# radio.net
KiCad netlist of a schematic drawn in Altium Designer
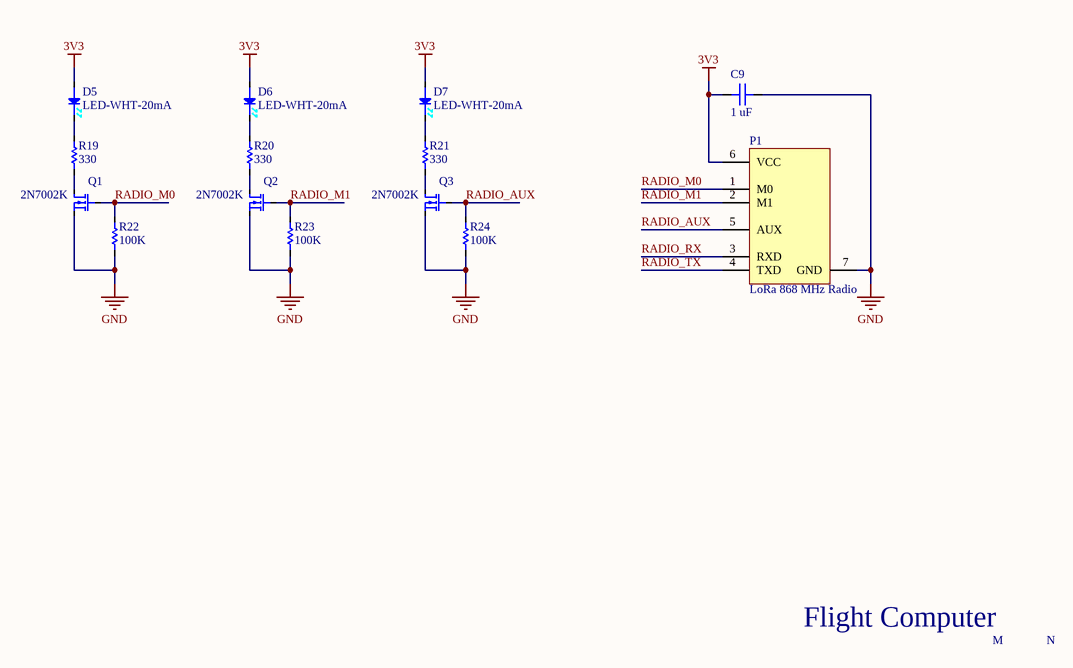
[diagram p0: radio.SchDoc]

(export (version "E")
  (design (tool "Eeschema 10.0.6"))
  (components
    (comp (ref "C9")
      (value "1 uF")
      (footprint "CAP-CER-0805-TALL")
      (description "±10%, 0805")
      (libsource (lib "passive") (part "CAP-CER-1uF-10V"))
    )
    (comp (ref "D5")
      (value "LED-WHT-20mA")
      (footprint "LED-0805")
      (description "2.2V, 0805")
      (libsource (lib "passive") (part "LED-WHT-20mA"))
    )
    (comp (ref "D6")
      (value "LED-WHT-20mA")
      (footprint "LED-0805")
      (description "2.2V, 0805")
      (libsource (lib "passive") (part "LED-WHT-20mA"))
    )
    (comp (ref "D7")
      (value "LED-WHT-20mA")
      (footprint "LED-0805")
      (description "2.2V, 0805")
      (libsource (lib "passive") (part "LED-WHT-20mA"))
    )
    (comp (ref "P1")
      (value "LoRa 868 MHz Radio")
      (footprint "LoRa Breakout")
      (description "UART Interface, 0.1\" Pitch, E32 (868T20D) chipset")
      (libsource (lib "connector") (part "868 MHz SX1276 LoRa Breakout"))
    )
    (comp (ref "Q1")
      (value "2N7002K")
      (footprint "SC-89")
      (description "N-Channel, SOT-23")
      (libsource (lib "ic") (part "NMOS-2.0VT-60VDS-300mA"))
    )
    (comp (ref "Q2")
      (value "2N7002K")
      (footprint "SC-89")
      (description "N-Channel, SOT-23")
      (libsource (lib "ic") (part "NMOS-2.0VT-60VDS-300mA"))
    )
    (comp (ref "Q3")
      (value "2N7002K")
      (footprint "SC-89")
      (description "N-Channel, SOT-23")
      (libsource (lib "ic") (part "NMOS-2.0VT-60VDS-300mA"))
    )
    (comp (ref "R19")
      (value "330")
      (footprint "RES-0805")
      (description "0805")
      (libsource (lib "passive") (part "RES-330-1/8W"))
    )
    (comp (ref "R20")
      (value "330")
      (footprint "RES-0805")
      (description "0805")
      (libsource (lib "passive") (part "RES-330-1/8W"))
    )
    (comp (ref "R21")
      (value "330")
      (footprint "RES-0805")
      (description "0805")
      (libsource (lib "passive") (part "RES-330-1/8W"))
    )
    (comp (ref "R22")
      (value "100K")
      (footprint "RES-0805")
      (description "0805")
      (libsource (lib "passive") (part "RES-100K-1/8W"))
    )
    (comp (ref "R23")
      (value "100K")
      (footprint "RES-0805")
      (description "0805")
      (libsource (lib "passive") (part "RES-100K-1/8W"))
    )
    (comp (ref "R24")
      (value "100K")
      (footprint "RES-0805")
      (description "0805")
      (libsource (lib "passive") (part "RES-100K-1/8W"))
    )
  )
  (nets
    (net (code "1") (name "/RADIO_AUX") (class "Default")
      (node (ref "P1") (pin "5") (pinfunction "AUX_5") (pintype "passive"))
      (node (ref "Q3") (pin "1") (pinfunction "G_1") (pintype "passive"))
      (node (ref "R24") (pin "2") (pinfunction "2_2") (pintype "passive"))
    )
    (net (code "2") (name "/RADIO_M0") (class "Default")
      (node (ref "P1") (pin "1") (pinfunction "M0_1") (pintype "passive"))
      (node (ref "Q1") (pin "1") (pinfunction "G_1") (pintype "passive"))
      (node (ref "R22") (pin "2") (pinfunction "2_2") (pintype "passive"))
    )
    (net (code "3") (name "/RADIO_M1") (class "Default")
      (node (ref "P1") (pin "2") (pinfunction "M1_2") (pintype "passive"))
      (node (ref "Q2") (pin "1") (pinfunction "G_1") (pintype "passive"))
      (node (ref "R23") (pin "2") (pinfunction "2_2") (pintype "passive"))
    )
    (net (code "4") (name "/RADIO_RX") (class "Default")
      (node (ref "P1") (pin "3") (pinfunction "RXD_3") (pintype "passive"))
    )
    (net (code "5") (name "/RADIO_TX") (class "Default")
      (node (ref "P1") (pin "4") (pinfunction "TXD_4") (pintype "passive"))
    )
    (net (code "6") (name "3V3") (class "Default")
      (node (ref "C9") (pin "1") (pinfunction "1_1") (pintype "passive"))
      (node (ref "D5") (pin "1") (pinfunction "CT_1") (pintype "passive"))
      (node (ref "D6") (pin "1") (pinfunction "CT_1") (pintype "passive"))
      (node (ref "D7") (pin "1") (pinfunction "CT_1") (pintype "passive"))
      (node (ref "P1") (pin "6") (pinfunction "VCC_6") (pintype "passive"))
    )
    (net (code "7") (name "GND") (class "Default")
      (node (ref "C9") (pin "2") (pinfunction "2_2") (pintype "passive"))
      (node (ref "P1") (pin "7") (pinfunction "GND_7") (pintype "passive"))
      (node (ref "Q1") (pin "2") (pinfunction "S_2") (pintype "passive"))
      (node (ref "Q2") (pin "2") (pinfunction "S_2") (pintype "passive"))
      (node (ref "Q3") (pin "2") (pinfunction "S_2") (pintype "passive"))
      (node (ref "R22") (pin "1") (pinfunction "1_1") (pintype "passive"))
      (node (ref "R23") (pin "1") (pinfunction "1_1") (pintype "passive"))
      (node (ref "R24") (pin "1") (pinfunction "1_1") (pintype "passive"))
    )
    (net (code "8") (name "Net-(D5-AN)") (class "Default")
      (node (ref "D5") (pin "2") (pinfunction "AN_2") (pintype "passive"))
      (node (ref "R19") (pin "2") (pinfunction "2_2") (pintype "passive"))
    )
    (net (code "9") (name "Net-(D6-AN)") (class "Default")
      (node (ref "D6") (pin "2") (pinfunction "AN_2") (pintype "passive"))
      (node (ref "R20") (pin "2") (pinfunction "2_2") (pintype "passive"))
    )
    (net (code "10") (name "Net-(D7-AN)") (class "Default")
      (node (ref "D7") (pin "2") (pinfunction "AN_2") (pintype "passive"))
      (node (ref "R21") (pin "2") (pinfunction "2_2") (pintype "passive"))
    )
    (net (code "11") (name "Net-(Q1-D)") (class "Default")
      (node (ref "Q1") (pin "3") (pinfunction "D_3") (pintype "passive"))
      (node (ref "R19") (pin "1") (pinfunction "1_1") (pintype "passive"))
    )
    (net (code "12") (name "Net-(Q2-D)") (class "Default")
      (node (ref "Q2") (pin "3") (pinfunction "D_3") (pintype "passive"))
      (node (ref "R20") (pin "1") (pinfunction "1_1") (pintype "passive"))
    )
    (net (code "13") (name "Net-(Q3-D)") (class "Default")
      (node (ref "Q3") (pin "3") (pinfunction "D_3") (pintype "passive"))
      (node (ref "R21") (pin "1") (pinfunction "1_1") (pintype "passive"))
    )
  )
)
